# ZVSChargeSource.net
KiCad netlist of a schematic drawn in Altium Designer
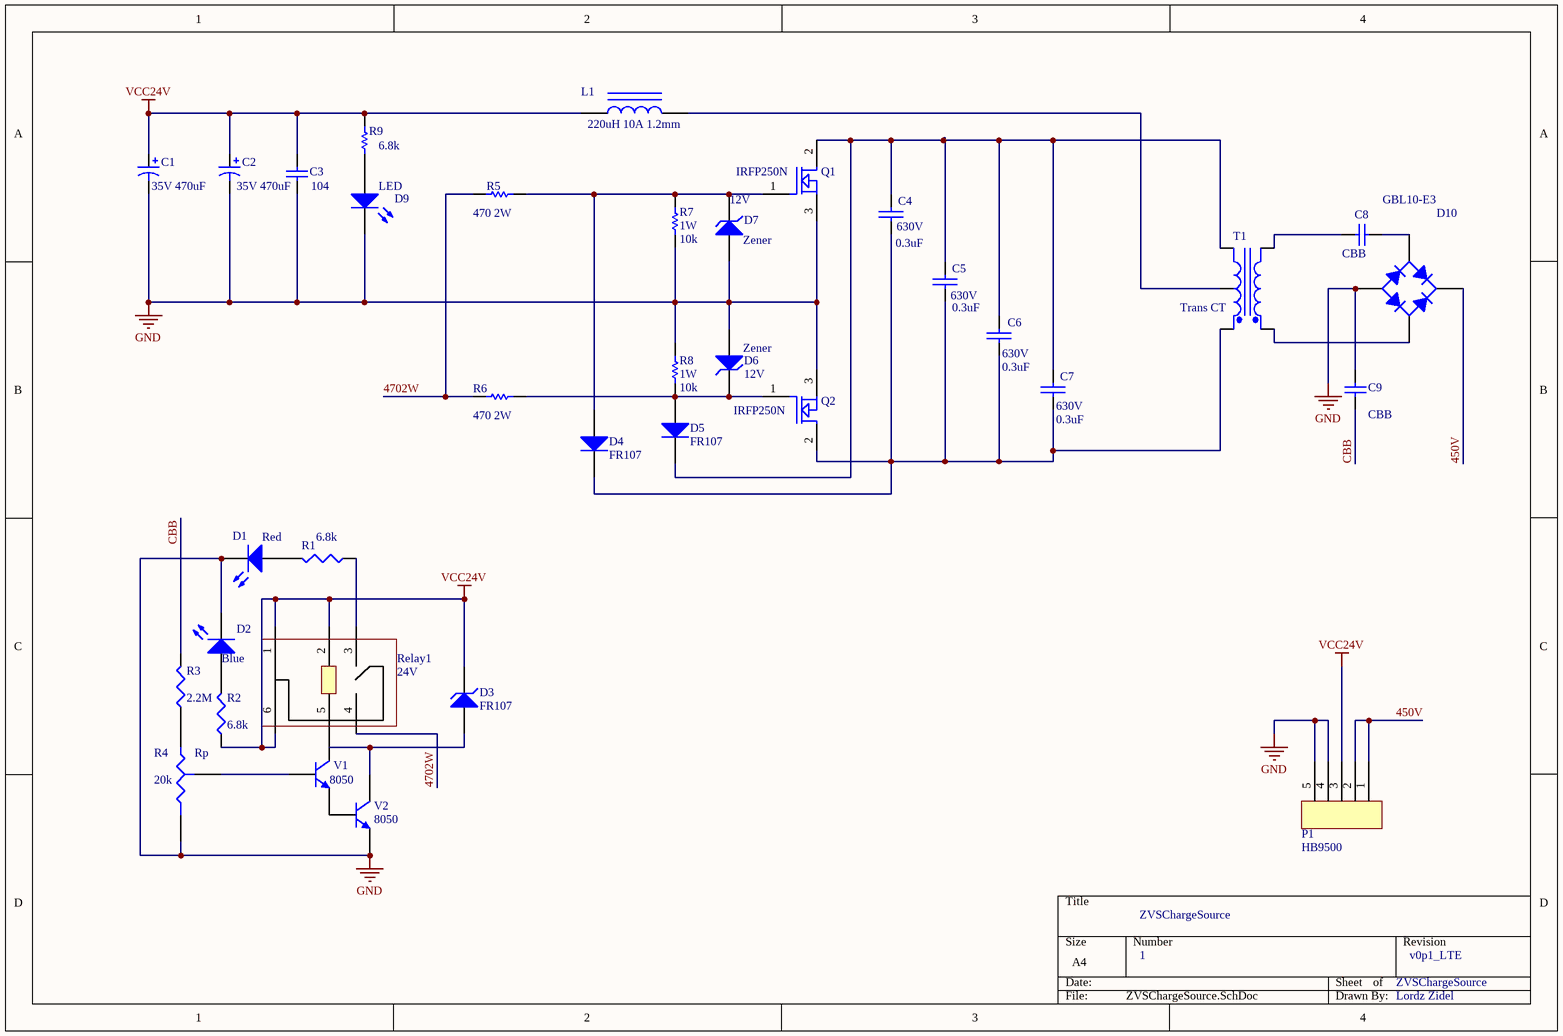
[diagram p0: ZVSChargeSource.SchDoc]

(export (version "E")
  (design (tool "Eeschema 10.0.6"))
  (components
    (comp (ref "C1")
      (value "35V 470uF")
      (footprint "C4_5_10mm")
      (description "Polarized Capacitor (Radial)")
      (fields (field (name "PUBLISHER") "Altium Limited"))
      (libsource (lib "Miscellaneous Devices") (part "Cap Pol1"))
    )
    (comp (ref "C2")
      (value "35V 470uF")
      (footprint "C4_5_10mm")
      (description "Polarized Capacitor (Radial)")
      (fields (field (name "PUBLISHER") "Altium Limited"))
      (libsource (lib "Miscellaneous Devices") (part "Cap Pol1"))
    )
    (comp (ref "C3")
      (value "104")
      (footprint "RAD-0.3")
      (description "Capacitor")
      (fields (field (name "PUBLISHER") "Altium Limited"))
      (libsource (lib "Miscellaneous Devices") (part "Cap"))
    )
    (comp (ref "C4")
      (value "630V")
      (footprint "MKP_Capacitor")
      (description "Capacitor")
      (fields (field (name "CAPACITANCE") "0.3uF"))
      (libsource (lib "电容") (part "普通电容"))
    )
    (comp (ref "C5")
      (value "630V")
      (footprint "MKP_Capacitor")
      (description "Capacitor")
      (fields (field (name "CAPACITANCE") "0.3uF"))
      (libsource (lib "电容") (part "普通电容"))
    )
    (comp (ref "C6")
      (value "630V")
      (footprint "MKP_Capacitor")
      (description "Capacitor")
      (fields (field (name "CAPACITANCE") "0.3uF"))
      (libsource (lib "电容") (part "普通电容"))
    )
    (comp (ref "C7")
      (value "630V")
      (footprint "MKP_Capacitor")
      (description "Capacitor")
      (fields (field (name "CAPACITANCE") "0.3uF"))
      (libsource (lib "电容") (part "普通电容"))
    )
    (comp (ref "C8")
      (value "CBB")
      (footprint "MKP_Capacitor")
      (description "Capacitor")
      (fields (field (name "PUBLISHER") "Altium Limited"))
      (libsource (lib "Miscellaneous Devices") (part "Cap"))
    )
    (comp (ref "C9")
      (value "CBB")
      (footprint "MKP_Capacitor")
      (description "Capacitor")
      (fields (field (name "PUBLISHER") "Altium Limited"))
      (libsource (lib "Miscellaneous Devices") (part "Cap"))
    )
    (comp (ref "D1")
      (value "~")
      (footprint "0805")
      (description "Typical RED, GREEN, YELLOW, AMBER GaAs LED")
      (fields (field (name "PUBLISHER") "Altium Limited"))
      (libsource (lib "Miscellaneous Devices") (part "LED2"))
    )
    (comp (ref "D2")
      (value "~")
      (footprint "0805")
      (description "Typical RED, GREEN, YELLOW, AMBER GaAs LED")
      (fields (field (name "PUBLISHER") "Altium Limited"))
      (libsource (lib "Miscellaneous Devices") (part "LED2"))
    )
    (comp (ref "D3")
      (value "FR107")
      (footprint "DIODE-0.4")
      (description "Zener Diode")
      (fields (field (name "PUBLISHER") "Altium Limited"))
      (libsource (lib "Miscellaneous Devices") (part "D Zener"))
    )
    (comp (ref "D4")
      (value "FR107")
      (footprint "DIODE-0.4")
      (description "1 Amp General Purpose Rectifier")
      (fields (field (name "PUBLISHER") "Altium Limited"))
      (libsource (lib "Miscellaneous Devices") (part "Diode 1N4007"))
    )
    (comp (ref "D5")
      (value "FR107")
      (footprint "DIODE-0.4")
      (description "1 Amp General Purpose Rectifier")
      (fields (field (name "PUBLISHER") "Altium Limited"))
      (libsource (lib "Miscellaneous Devices") (part "Diode 1N4007"))
    )
    (comp (ref "D6")
      (value "12V")
      (footprint "DIODE-0.4")
      (description "Zener Diode")
      (fields (field (name "PUBLISHER") "Altium Limited"))
      (libsource (lib "Miscellaneous Devices") (part "D Zener"))
    )
    (comp (ref "D7")
      (value "12V")
      (footprint "DIODE-0.4")
      (description "Zener Diode")
      (fields (field (name "PUBLISHER") "Altium Limited"))
      (libsource (lib "Miscellaneous Devices") (part "D Zener"))
    )
    (comp (ref "D9")
      (value "~")
      (footprint "0805")
      (description "Typical BLUE SiC LED")
      (fields (field (name "PUBLISHER") "Altium Limited"))
      (libsource (lib "Miscellaneous Devices") (part "LED3"))
    )
    (comp (ref "D10")
      (value "GBL10-E3")
      (footprint "GBL10-E3")
      (description "Full Wave Diode Bridge")
      (fields (field (name "PUBLISHER") "Altium Limited"))
      (libsource (lib "Miscellaneous Devices") (part "Bridge1"))
    )
    (comp (ref "L1")
      (value "220uH 10A 1.2mm")
      (footprint "HBL_30_10_H")
      (description "Magnetic-Core Inductor")
      (fields (field (name "PUBLISHER") "Altium Limited"))
      (libsource (lib "Miscellaneous Devices") (part "Inductor Iron"))
    )
    (comp (ref "P1")
      (value "HB9500")
      (footprint "CJ_10x5")
      (libsource (lib "WKVER_Private") (part "WJ5P_381"))
    )
    (comp (ref "Q1")
      (value "IRFP250N")
      (footprint "TO-247AC_ZCEDGE")
      (libsource (lib "场效应管及可控硅") (part "MOSFET N"))
    )
    (comp (ref "Q2")
      (value "IRFP250N")
      (footprint "TO-247AC_ZCEDGE")
      (libsource (lib "场效应管及可控硅") (part "MOSFET N"))
    )
    (comp (ref "R1")
      (value "6.8k")
      (footprint "0805R")
      (description "Resistor")
      (fields (field (name "PUBLISHER") "Altium Limited"))
      (libsource (lib "Miscellaneous Devices") (part "Res3"))
    )
    (comp (ref "R2")
      (value "6.8k")
      (footprint "0805R")
      (description "Resistor")
      (fields (field (name "PUBLISHER") "Altium Limited"))
      (libsource (lib "Miscellaneous Devices") (part "Res3"))
    )
    (comp (ref "R3")
      (value "2.2M")
      (footprint "0805R")
      (description "Resistor")
      (fields (field (name "PUBLISHER") "Altium Limited"))
      (libsource (lib "Miscellaneous Devices") (part "Res3"))
    )
    (comp (ref "R4")
      (value "Rp")
      (footprint "ResTap3296")
      (description "Tapped Resistor")
      (fields (field (name "ALTIUM_VALUE") "20k") (field (name "PUBLISHER") "Altium Limited"))
      (libsource (lib "Miscellaneous Devices") (part "Res Tap"))
    )
    (comp (ref "R5")
      (value "470 2W")
      (footprint "2WZC")
      (description "Resistor")
      (fields (field (name "PUBLISHER") "Altium Limited"))
      (libsource (lib "Miscellaneous Devices") (part "Res1"))
    )
    (comp (ref "R6")
      (value "470 2W")
      (footprint "2WZC")
      (description "Resistor")
      (fields (field (name "PUBLISHER") "Altium Limited"))
      (libsource (lib "Miscellaneous Devices") (part "Res1"))
    )
    (comp (ref "R7")
      (value "1W")
      (footprint "1WZC")
      (description "Resistor")
      (fields (field (name "ALTIUM_VALUE") "10k") (field (name "PUBLISHER") "Altium Limited"))
      (libsource (lib "Miscellaneous Devices") (part "Res1"))
    )
    (comp (ref "R8")
      (value "1W")
      (footprint "1WZC")
      (description "Resistor")
      (fields (field (name "ALTIUM_VALUE") "10k") (field (name "PUBLISHER") "Altium Limited"))
      (libsource (lib "Miscellaneous Devices") (part "Res1"))
    )
    (comp (ref "R9")
      (value "6.8k")
      (footprint "AXIAL-0.3")
      (description "Resistor")
      (fields (field (name "PUBLISHER") "Altium Limited"))
      (libsource (lib "Miscellaneous Devices") (part "Res1"))
    )
    (comp (ref "Relay1")
      (value "Relay?")
      (footprint "Relay_HK4100F_6p")
      (libsource (lib "WKVER_Private") (part "Relay_HK4100F_6p"))
    )
    (comp (ref "T1")
      (value "Trans CT")
      (footprint "TRF_5")
      (description "Center-Tapped Transformer (Coupled Inductor Model)")
      (fields (field (name "PUBLISHER") "Altium Limited"))
      (libsource (lib "Miscellaneous Devices") (part "Trans CT"))
    )
    (comp (ref "V1")
      (value "8050")
      (footprint "sot-23")
      (description "NPN Bipolar Transistor")
      (fields (field (name "PUBLISHER") "Altium Limited"))
      (libsource (lib "RobotBrain_V0.50") (part "NPN"))
    )
    (comp (ref "V2")
      (value "8050")
      (footprint "sot-23")
      (description "NPN Bipolar Transistor")
      (fields (field (name "PUBLISHER") "Altium Limited"))
      (libsource (lib "RobotBrain_V0.50") (part "NPN"))
    )
  )
  (nets
    (net (code "1") (name "/450V") (class "Default")
      (node (ref "D10") (pin "1") (pinfunction "K_1") (pintype "passive"))
      (node (ref "P1") (pin "1") (pintype "passive"))
      (node (ref "P1") (pin "2") (pintype "passive"))
    )
    (net (code "2") (name "/4702W") (class "Default")
      (node (ref "R5") (pin "2") (pinfunction "2_2") (pintype "passive"))
      (node (ref "R6") (pin "2") (pinfunction "2_2") (pintype "passive"))
      (node (ref "Relay1") (pin "4") (pinfunction "4_4") (pintype "passive"))
    )
    (net (code "3") (name "/CBB") (class "Default")
      (node (ref "C9") (pin "1") (pinfunction "1_1") (pintype "passive"))
      (node (ref "R3") (pin "2") (pinfunction "2_2") (pintype "passive"))
    )
    (net (code "4") (name "GND") (class "Default")
      (node (ref "C1") (pin "2") (pinfunction "2_2") (pintype "passive"))
      (node (ref "C2") (pin "2") (pinfunction "2_2") (pintype "passive"))
      (node (ref "C3") (pin "1") (pinfunction "1_1") (pintype "passive"))
      (node (ref "C9") (pin "2") (pinfunction "2_2") (pintype "passive"))
      (node (ref "D1") (pin "2") (pinfunction "K_2") (pintype "passive"))
      (node (ref "D10") (pin "3") (pinfunction "A_3") (pintype "passive"))
      (node (ref "D2") (pin "2") (pinfunction "K_2") (pintype "passive"))
      (node (ref "D6") (pin "1") (pinfunction "A_1") (pintype "passive"))
      (node (ref "D7") (pin "1") (pinfunction "A_1") (pintype "passive"))
      (node (ref "D9") (pin "2") (pinfunction "K_2") (pintype "passive"))
      (node (ref "P1") (pin "4") (pintype "passive"))
      (node (ref "P1") (pin "5") (pintype "passive"))
      (node (ref "Q1") (pin "3") (pinfunction "S_3") (pintype "passive"))
      (node (ref "Q2") (pin "3") (pinfunction "S_3") (pintype "passive"))
      (node (ref "R4") (pin "2") (pinfunction "B_2") (pintype "passive"))
      (node (ref "R7") (pin "2") (pinfunction "2_2") (pintype "passive"))
      (node (ref "R8") (pin "1") (pinfunction "1_1") (pintype "passive"))
      (node (ref "V2") (pin "2") (pinfunction "E_2") (pintype "passive"))
    )
    (net (code "5") (name "Net-(C8-Pad2)") (class "Default")
      (node (ref "C8") (pin "2") (pinfunction "2_2") (pintype "passive"))
      (node (ref "D10") (pin "4") (pinfunction "C_4") (pintype "passive"))
    )
    (net (code "6") (name "Net-(D1-A)") (class "Default")
      (node (ref "D1") (pin "1") (pinfunction "A_1") (pintype "passive"))
      (node (ref "R1") (pin "2") (pinfunction "2_2") (pintype "passive"))
    )
    (net (code "7") (name "Net-(D2-A)") (class "Default")
      (node (ref "D2") (pin "1") (pinfunction "A_1") (pintype "passive"))
      (node (ref "R2") (pin "2") (pinfunction "2_2") (pintype "passive"))
    )
    (net (code "8") (name "Net-(D3-A)") (class "Default")
      (node (ref "D3") (pin "1") (pinfunction "A_1") (pintype "passive"))
      (node (ref "V2") (pin "3") (pinfunction "C_3") (pintype "passive"))
    )
    (net (code "9") (name "Net-(D4-A)") (class "Default")
      (node (ref "D4") (pin "1") (pinfunction "A_1") (pintype "passive"))
      (node (ref "D7") (pin "2") (pinfunction "K_2") (pintype "passive"))
      (node (ref "Q1") (pin "1") (pinfunction "G_1") (pintype "passive"))
      (node (ref "R5") (pin "1") (pinfunction "1_1") (pintype "passive"))
      (node (ref "R7") (pin "1") (pinfunction "1_1") (pintype "passive"))
    )
    (net (code "10") (name "Net-(D4-K)") (class "Default")
      (node (ref "C4") (pin "2") (pinfunction "2_2") (pintype "passive"))
      (node (ref "C5") (pin "2") (pinfunction "2_2") (pintype "passive"))
      (node (ref "C6") (pin "2") (pinfunction "2_2") (pintype "passive"))
      (node (ref "C7") (pin "2") (pinfunction "2_2") (pintype "passive"))
      (node (ref "D4") (pin "2") (pinfunction "K_2") (pintype "passive"))
      (node (ref "Q2") (pin "2") (pinfunction "D_2") (pintype "passive"))
      (node (ref "T1") (pin "3") (pinfunction "Sec+_3") (pintype "passive"))
    )
    (net (code "11") (name "Net-(D5-A)") (class "Default")
      (node (ref "D5") (pin "1") (pinfunction "A_1") (pintype "passive"))
      (node (ref "D6") (pin "2") (pinfunction "K_2") (pintype "passive"))
      (node (ref "Q2") (pin "1") (pinfunction "G_1") (pintype "passive"))
      (node (ref "R6") (pin "1") (pinfunction "1_1") (pintype "passive"))
      (node (ref "R8") (pin "2") (pinfunction "2_2") (pintype "passive"))
    )
    (net (code "12") (name "Net-(D5-K)") (class "Default")
      (node (ref "C4") (pin "1") (pinfunction "1_1") (pintype "passive"))
      (node (ref "C5") (pin "1") (pinfunction "1_1") (pintype "passive"))
      (node (ref "C6") (pin "1") (pinfunction "1_1") (pintype "passive"))
      (node (ref "C7") (pin "1") (pinfunction "1_1") (pintype "passive"))
      (node (ref "D5") (pin "2") (pinfunction "K_2") (pintype "passive"))
      (node (ref "Q1") (pin "2") (pinfunction "D_2") (pintype "passive"))
      (node (ref "T1") (pin "5") (pinfunction "Sec-_5") (pintype "passive"))
    )
    (net (code "13") (name "Net-(D9-A)") (class "Default")
      (node (ref "D9") (pin "1") (pinfunction "A_1") (pintype "passive"))
      (node (ref "R9") (pin "1") (pinfunction "1_1") (pintype "passive"))
    )
    (net (code "14") (name "Net-(R1-Pad1)") (class "Default")
      (node (ref "R1") (pin "1") (pinfunction "1_1") (pintype "passive"))
      (node (ref "Relay1") (pin "3") (pinfunction "3_3") (pintype "passive"))
    )
    (net (code "15") (name "Net-(R4-A)") (class "Default")
      (node (ref "R3") (pin "1") (pinfunction "1_1") (pintype "passive"))
      (node (ref "R4") (pin "1") (pinfunction "A_1") (pintype "passive"))
    )
    (net (code "16") (name "Net-(R4-TAP)") (class "Default")
      (node (ref "R4") (pin "3") (pinfunction "TAP_3") (pintype "passive"))
      (node (ref "V1") (pin "1") (pinfunction "B_1") (pintype "passive"))
    )
    (net (code "17") (name "Net-(T1-Pri+)") (class "Default")
      (node (ref "D10") (pin "2") (pinfunction "C_2") (pintype "passive"))
      (node (ref "T1") (pin "1") (pinfunction "Pri+_1") (pintype "passive"))
    )
    (net (code "18") (name "Net-(T1-Pri-)") (class "Default")
      (node (ref "C8") (pin "1") (pinfunction "1_1") (pintype "passive"))
      (node (ref "T1") (pin "2") (pinfunction "Pri-_2") (pintype "passive"))
    )
    (net (code "19") (name "Net-(T1-SecCT)") (class "Default")
      (node (ref "L1") (pin "2") (pinfunction "2_2") (pintype "passive"))
      (node (ref "T1") (pin "4") (pinfunction "SecCT_4") (pintype "passive"))
    )
    (net (code "20") (name "Net-(V1-C)") (class "Default")
      (node (ref "Relay1") (pin "5") (pinfunction "5_5") (pintype "passive"))
      (node (ref "V1") (pin "3") (pinfunction "C_3") (pintype "passive"))
    )
    (net (code "21") (name "Net-(V1-E)") (class "Default")
      (node (ref "V1") (pin "2") (pinfunction "E_2") (pintype "passive"))
      (node (ref "V2") (pin "1") (pinfunction "B_1") (pintype "passive"))
    )
    (net (code "22") (name "VCC24V") (class "Default")
      (node (ref "C1") (pin "1") (pinfunction "1_1") (pintype "passive"))
      (node (ref "C2") (pin "1") (pinfunction "1_1") (pintype "passive"))
      (node (ref "C3") (pin "2") (pinfunction "2_2") (pintype "passive"))
      (node (ref "D3") (pin "2") (pinfunction "K_2") (pintype "passive"))
      (node (ref "L1") (pin "1") (pinfunction "1_1") (pintype "passive"))
      (node (ref "P1") (pin "3") (pintype "passive"))
      (node (ref "R2") (pin "1") (pinfunction "1_1") (pintype "passive"))
      (node (ref "R9") (pin "2") (pinfunction "2_2") (pintype "passive"))
      (node (ref "Relay1") (pin "1") (pinfunction "1_1") (pintype "passive"))
      (node (ref "Relay1") (pin "2") (pinfunction "2_2") (pintype "passive"))
      (node (ref "Relay1") (pin "6") (pinfunction "6_6") (pintype "passive"))
    )
  )
)
